# PowerBricksBoard1_X14.net
KiCad netlist of a schematic drawn in EAGLE
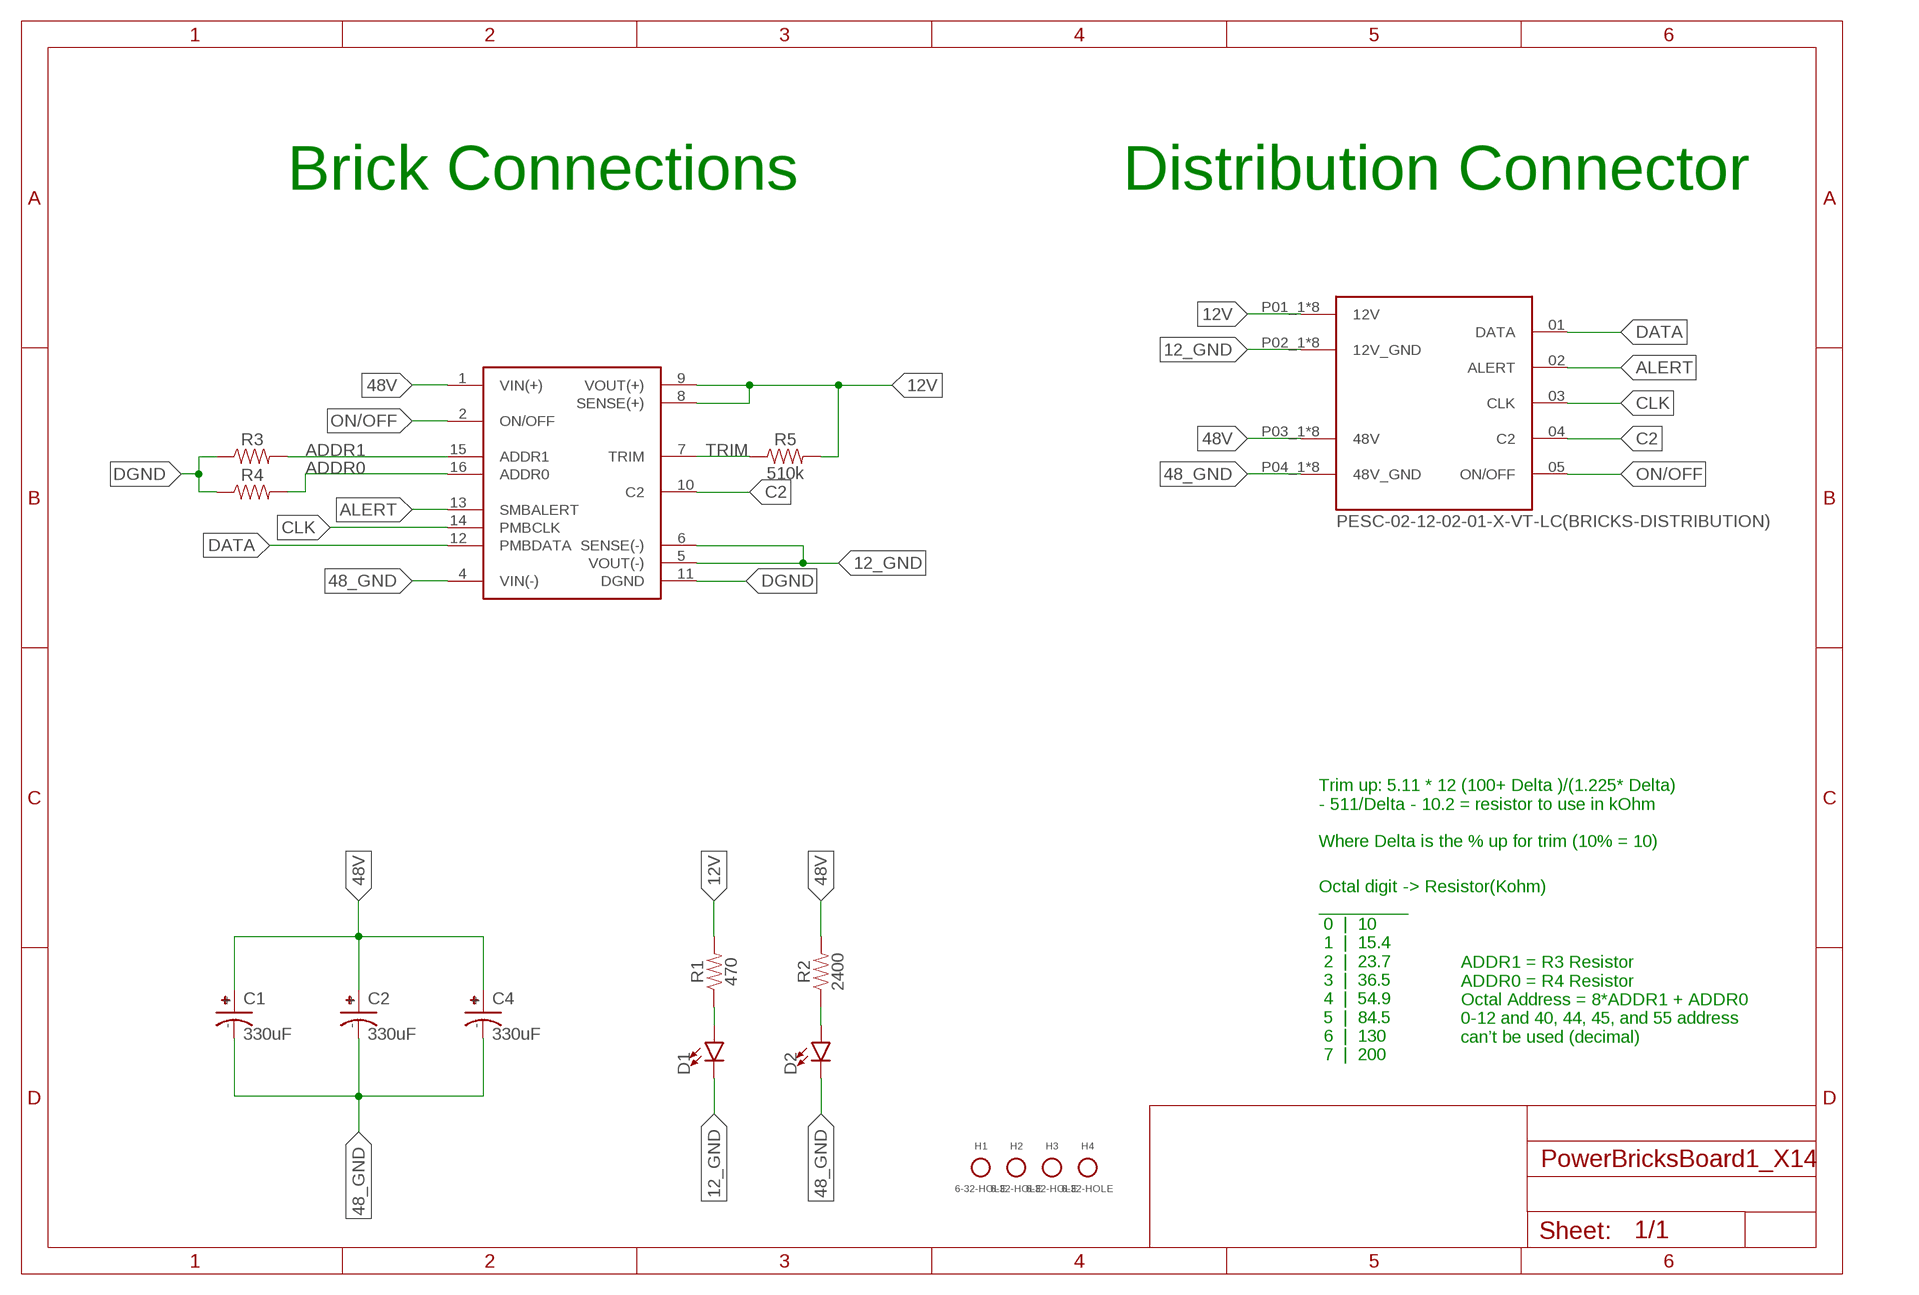
[diagram p0: schematic, sheet 1]

(export (version "E")
  (design (tool "Eeschema 10.0.6"))
  (components
    (comp (ref "C1")
      (value "330uF")
      (footprint "eagle-import:CAPAE1030X1050N")
      (fields
        (field (name "ARROW_PART_NUMBER") "UCM1H331MNL1GS")
        (field (name "MOUSER_PART_NUMBER") "647-UCM1H331MNL1GS")
      )
      (libsource (lib "eagle-import") (part "UCM1H331MNL1GS"))
    )
    (comp (ref "C2")
      (value "330uF")
      (footprint "eagle-import:CAPAE1030X1050N")
      (fields
        (field (name "ARROW_PART_NUMBER") "UCM1H331MNL1GS")
        (field (name "MOUSER_PART_NUMBER") "647-UCM1H331MNL1GS")
      )
      (libsource (lib "eagle-import") (part "UCM1H331MNL1GS"))
    )
    (comp (ref "C4")
      (value "330uF")
      (footprint "eagle-import:CAPAE1030X1050N")
      (fields
        (field (name "ARROW_PART_NUMBER") "UCM1H331MNL1GS")
        (field (name "MOUSER_PART_NUMBER") "647-UCM1H331MNL1GS")
      )
      (libsource (lib "eagle-import") (part "UCM1H331MNL1GS"))
    )
    (comp (ref "D1")
      (value "LED0603")
      (footprint "eagle-import:LED-0603")
      (libsource (lib "eagle-import") (part "LED0603"))
    )
    (comp (ref "D2")
      (value "LED0603")
      (footprint "eagle-import:LED-0603")
      (libsource (lib "eagle-import") (part "LED0603"))
    )
    (comp (ref "H1")
      (value "6-32-HOLE")
      (footprint "eagle-import:6-32-HOLE")
      (libsource (lib "eagle-import") (part "6-32-HOLE"))
    )
    (comp (ref "H2")
      (value "6-32-HOLE")
      (footprint "eagle-import:6-32-HOLE")
      (libsource (lib "eagle-import") (part "6-32-HOLE"))
    )
    (comp (ref "H3")
      (value "6-32-HOLE")
      (footprint "eagle-import:6-32-HOLE")
      (libsource (lib "eagle-import") (part "6-32-HOLE"))
    )
    (comp (ref "H4")
      (value "6-32-HOLE")
      (footprint "eagle-import:6-32-HOLE")
      (libsource (lib "eagle-import") (part "6-32-HOLE"))
    )
    (comp (ref "J1")
      (value "PESC-02-12-02-01-X-VT-LC(BRICKS-DISTRIBUTION)")
      (footprint "eagle-import:SAMTEC_PESC-02-12-02-01-X-VT-LC(B-D)")
      (fields (field (name "MANUFACTURER") "Samtec"))
      (libsource (lib "eagle-import") (part "PESC-02-12-02-01-X-VT-LC(BRICKS-DISTRIBUTION)"))
    )
    (comp (ref "R1")
      (value "470")
      (footprint "eagle-import:0603")
      (libsource (lib "eagle-import") (part "RESISTOR0603"))
    )
    (comp (ref "R2")
      (value "2400")
      (footprint "eagle-import:0603")
      (libsource (lib "eagle-import") (part "RESISTOR0603"))
    )
    (comp (ref "R3")
      (value "RESISTOR0603")
      (footprint "eagle-import:0603")
      (libsource (lib "eagle-import") (part "RESISTOR0603"))
    )
    (comp (ref "R4")
      (value "RESISTOR0603")
      (footprint "eagle-import:0603")
      (libsource (lib "eagle-import") (part "RESISTOR0603"))
    )
    (comp (ref "R5")
      (value "510k")
      (footprint "eagle-import:0603")
      (libsource (lib "eagle-import") (part "RESISTOR0603"))
    )
    (comp (ref "U$2")
      (value "Q48SC12050NRDH")
      (footprint "eagle-import:Q48SC12050NRDH")
      (libsource (lib "eagle-import") (part "Q48SC12050NRDH"))
    )
  )
  (nets
    (net (code "1") (name "/ADDR0") (class "Default")
      (node (ref "R4") (pin "2") (pinfunction "2_2") (pintype "passive"))
      (node (ref "U$2") (pin "16") (pinfunction "ADDR0_16") (pintype "bidirectional"))
    )
    (net (code "2") (name "/ADDR1") (class "Default")
      (node (ref "R3") (pin "2") (pinfunction "2_2") (pintype "passive"))
      (node (ref "U$2") (pin "15") (pinfunction "ADDR1_15") (pintype "bidirectional"))
    )
    (net (code "3") (name "/TRIM") (class "Default")
      (node (ref "R5") (pin "1") (pinfunction "1_1") (pintype "passive"))
      (node (ref "U$2") (pin "7") (pinfunction "TRIM_7") (pintype "bidirectional"))
    )
    (net (code "4") (name "12V") (class "Default")
      (node (ref "J1") (pin "P01_1") (pinfunction "12V_P01_1") (pintype "power_in"))
      (node (ref "J1") (pin "P01_2") (pinfunction "12V_P01_2") (pintype "power_in"))
      (node (ref "J1") (pin "P01_3") (pinfunction "12V_P01_3") (pintype "power_in"))
      (node (ref "J1") (pin "P01_4") (pinfunction "12V_P01_4") (pintype "power_in"))
      (node (ref "J1") (pin "P01_5") (pinfunction "12V_P01_5") (pintype "power_in"))
      (node (ref "J1") (pin "P01_6") (pinfunction "12V_P01_6") (pintype "power_in"))
      (node (ref "J1") (pin "P01_7") (pinfunction "12V_P01_7") (pintype "power_in"))
      (node (ref "J1") (pin "P01_8") (pinfunction "12V_P01_8") (pintype "power_in"))
      (node (ref "R1") (pin "2") (pinfunction "2_2") (pintype "passive"))
      (node (ref "R5") (pin "2") (pinfunction "2_2") (pintype "passive"))
      (node (ref "U$2") (pin "8") (pinfunction "SENSE(+)_8") (pintype "bidirectional"))
      (node (ref "U$2") (pin "9") (pinfunction "VOUT(+)_9") (pintype "bidirectional"))
    )
    (net (code "5") (name "12_GND") (class "Default")
      (node (ref "D1") (pin "C") (pinfunction "C_C") (pintype "passive"))
      (node (ref "J1") (pin "P02_1") (pinfunction "12V_GND_P02_1") (pintype "power_in"))
      (node (ref "J1") (pin "P02_2") (pinfunction "12V_GND_P02_2") (pintype "power_in"))
      (node (ref "J1") (pin "P02_3") (pinfunction "12V_GND_P02_3") (pintype "power_in"))
      (node (ref "J1") (pin "P02_4") (pinfunction "12V_GND_P02_4") (pintype "power_in"))
      (node (ref "J1") (pin "P02_5") (pinfunction "12V_GND_P02_5") (pintype "power_in"))
      (node (ref "J1") (pin "P02_6") (pinfunction "12V_GND_P02_6") (pintype "power_in"))
      (node (ref "J1") (pin "P02_7") (pinfunction "12V_GND_P02_7") (pintype "power_in"))
      (node (ref "J1") (pin "P02_8") (pinfunction "12V_GND_P02_8") (pintype "power_in"))
      (node (ref "U$2") (pin "5") (pinfunction "VOUT(-)_5") (pintype "bidirectional"))
      (node (ref "U$2") (pin "6") (pinfunction "SENSE(-)_6") (pintype "bidirectional"))
    )
    (net (code "6") (name "48V") (class "Default")
      (node (ref "C1") (pin "+") (pinfunction "+_+") (pintype "bidirectional"))
      (node (ref "C2") (pin "+") (pinfunction "+_+") (pintype "bidirectional"))
      (node (ref "C4") (pin "+") (pinfunction "+_+") (pintype "bidirectional"))
      (node (ref "J1") (pin "P03_1") (pinfunction "48V_P03_1") (pintype "power_in"))
      (node (ref "J1") (pin "P03_2") (pinfunction "48V_P03_2") (pintype "power_in"))
      (node (ref "J1") (pin "P03_3") (pinfunction "48V_P03_3") (pintype "power_in"))
      (node (ref "J1") (pin "P03_4") (pinfunction "48V_P03_4") (pintype "power_in"))
      (node (ref "J1") (pin "P03_5") (pinfunction "48V_P03_5") (pintype "power_in"))
      (node (ref "J1") (pin "P03_6") (pinfunction "48V_P03_6") (pintype "power_in"))
      (node (ref "J1") (pin "P03_7") (pinfunction "48V_P03_7") (pintype "power_in"))
      (node (ref "J1") (pin "P03_8") (pinfunction "48V_P03_8") (pintype "power_in"))
      (node (ref "R2") (pin "2") (pinfunction "2_2") (pintype "passive"))
      (node (ref "U$2") (pin "1") (pinfunction "VIN(+)_1") (pintype "bidirectional"))
    )
    (net (code "7") (name "48_GND") (class "Default")
      (node (ref "C1") (pin "-") (pinfunction "-_-") (pintype "bidirectional"))
      (node (ref "C2") (pin "-") (pinfunction "-_-") (pintype "bidirectional"))
      (node (ref "C4") (pin "-") (pinfunction "-_-") (pintype "bidirectional"))
      (node (ref "D2") (pin "C") (pinfunction "C_C") (pintype "passive"))
      (node (ref "J1") (pin "P04_1") (pinfunction "48V_GND_P04_1") (pintype "power_in"))
      (node (ref "J1") (pin "P04_2") (pinfunction "48V_GND_P04_2") (pintype "power_in"))
      (node (ref "J1") (pin "P04_3") (pinfunction "48V_GND_P04_3") (pintype "power_in"))
      (node (ref "J1") (pin "P04_4") (pinfunction "48V_GND_P04_4") (pintype "power_in"))
      (node (ref "J1") (pin "P04_5") (pinfunction "48V_GND_P04_5") (pintype "power_in"))
      (node (ref "J1") (pin "P04_6") (pinfunction "48V_GND_P04_6") (pintype "power_in"))
      (node (ref "J1") (pin "P04_7") (pinfunction "48V_GND_P04_7") (pintype "power_in"))
      (node (ref "J1") (pin "P04_8") (pinfunction "48V_GND_P04_8") (pintype "power_in"))
      (node (ref "U$2") (pin "4") (pinfunction "VIN(-)_4") (pintype "bidirectional"))
    )
    (net (code "8") (name "ALERT") (class "Default")
      (node (ref "J1") (pin "02") (pinfunction "ALERT_02") (pintype "passive"))
      (node (ref "U$2") (pin "13") (pinfunction "SMBALERT_13") (pintype "bidirectional"))
    )
    (net (code "9") (name "C2") (class "Default")
      (node (ref "J1") (pin "04") (pinfunction "C2_04") (pintype "passive"))
      (node (ref "U$2") (pin "10") (pinfunction "C2_10") (pintype "bidirectional"))
    )
    (net (code "10") (name "CLK") (class "Default")
      (node (ref "J1") (pin "03") (pinfunction "CLK_03") (pintype "passive"))
      (node (ref "U$2") (pin "14") (pinfunction "PMBCLK_14") (pintype "bidirectional"))
    )
    (net (code "11") (name "DATA") (class "Default")
      (node (ref "J1") (pin "01") (pinfunction "DATA_01") (pintype "passive"))
      (node (ref "U$2") (pin "12") (pinfunction "PMBDATA_12") (pintype "bidirectional"))
    )
    (net (code "12") (name "DGND") (class "Default")
      (node (ref "R3") (pin "1") (pinfunction "1_1") (pintype "passive"))
      (node (ref "R4") (pin "1") (pinfunction "1_1") (pintype "passive"))
      (node (ref "U$2") (pin "11") (pinfunction "DGND_11") (pintype "bidirectional"))
    )
    (net (code "13") (name "Net-(D1-PadA)") (class "Default")
      (node (ref "D1") (pin "A") (pinfunction "A_A") (pintype "passive"))
      (node (ref "R1") (pin "1") (pinfunction "1_1") (pintype "passive"))
    )
    (net (code "14") (name "Net-(D2-PadA)") (class "Default")
      (node (ref "D2") (pin "A") (pinfunction "A_A") (pintype "passive"))
      (node (ref "R2") (pin "1") (pinfunction "1_1") (pintype "passive"))
    )
    (net (code "15") (name "ON{slash}OFF") (class "Default")
      (node (ref "J1") (pin "05") (pinfunction "ON/OFF_05") (pintype "passive"))
      (node (ref "U$2") (pin "2") (pinfunction "ON/OFF_2") (pintype "bidirectional"))
    )
  )
)
